# Tarjeta.net
KiCad netlist of a schematic drawn in EAGLE
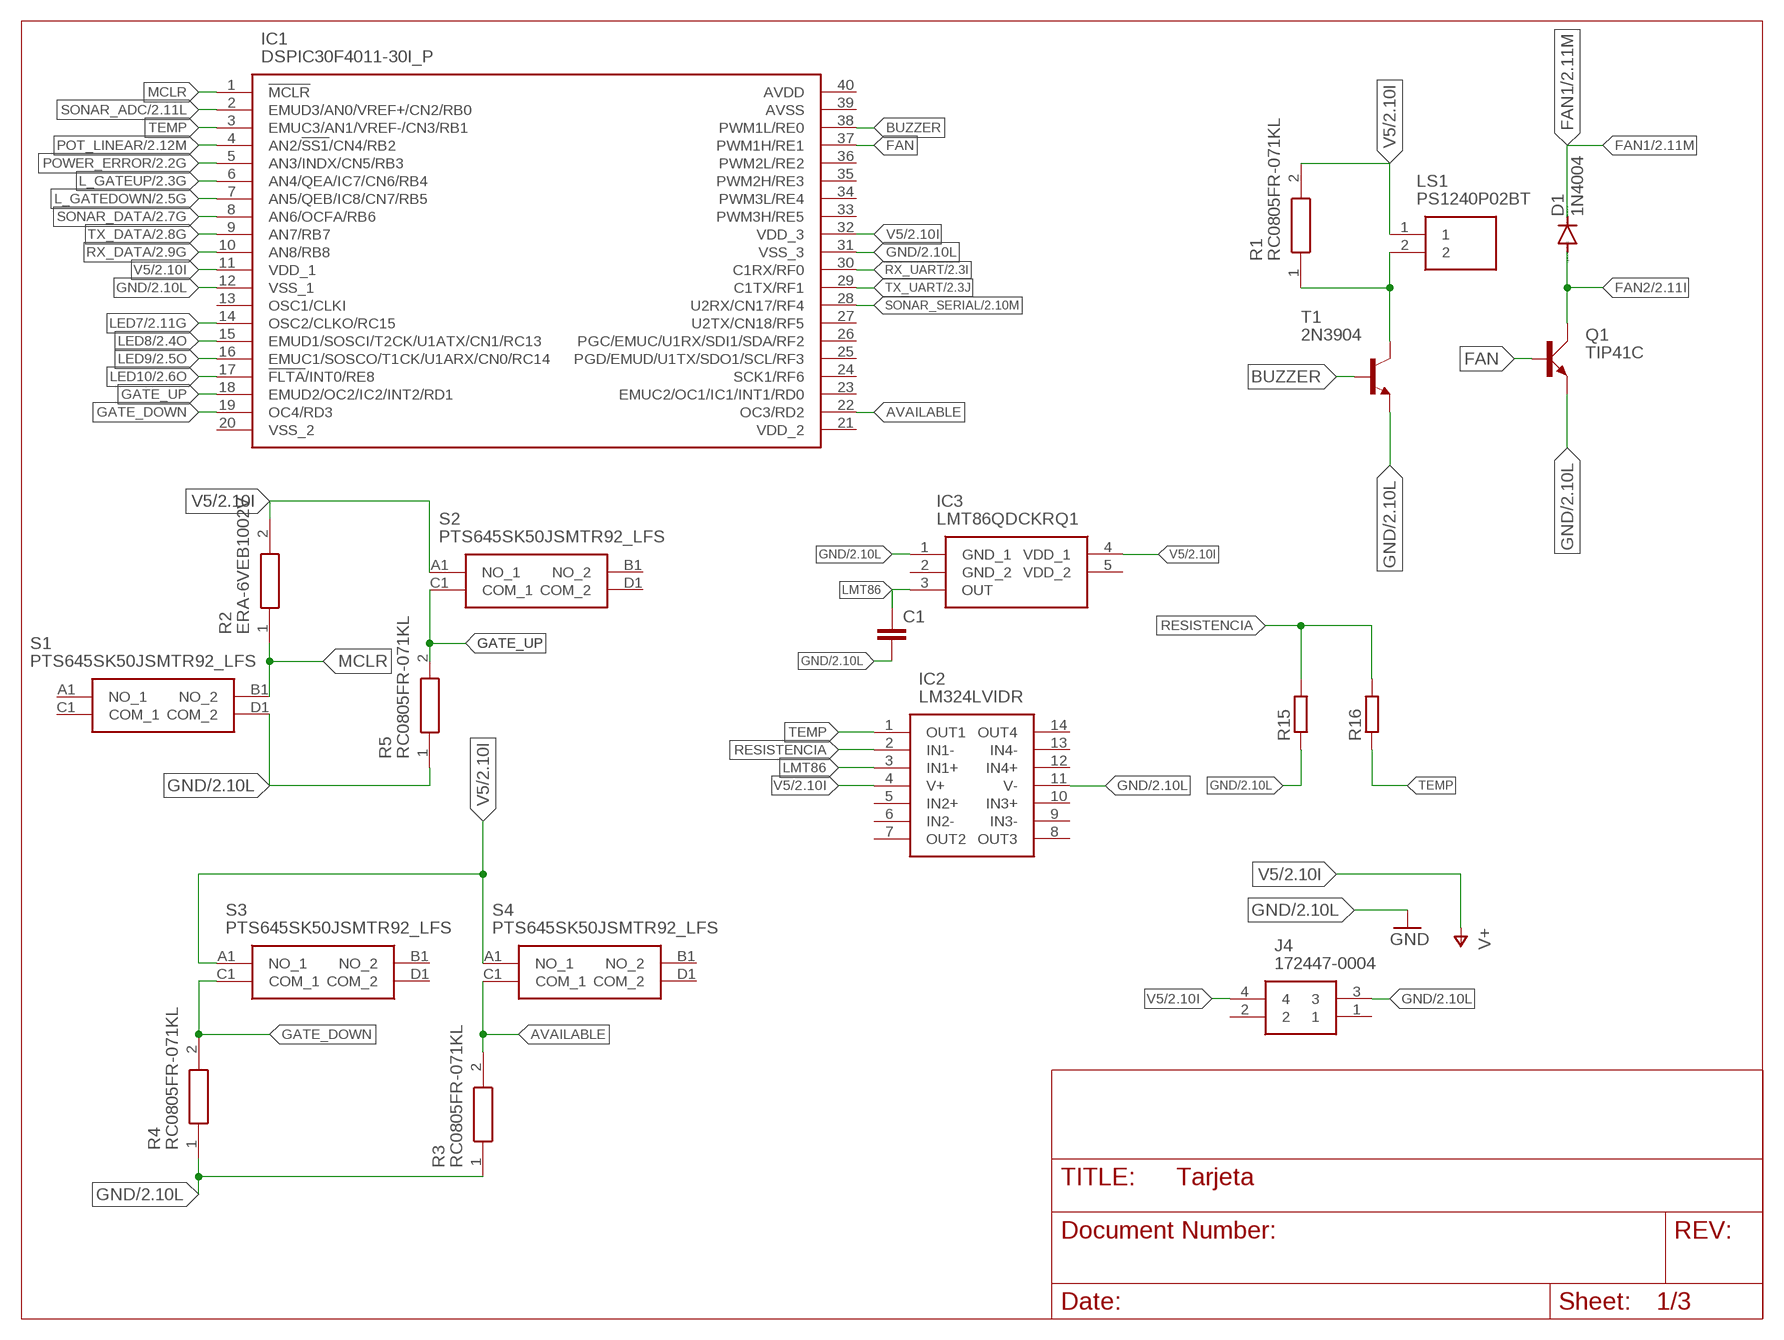
[diagram p0: schematic, sheet 1]
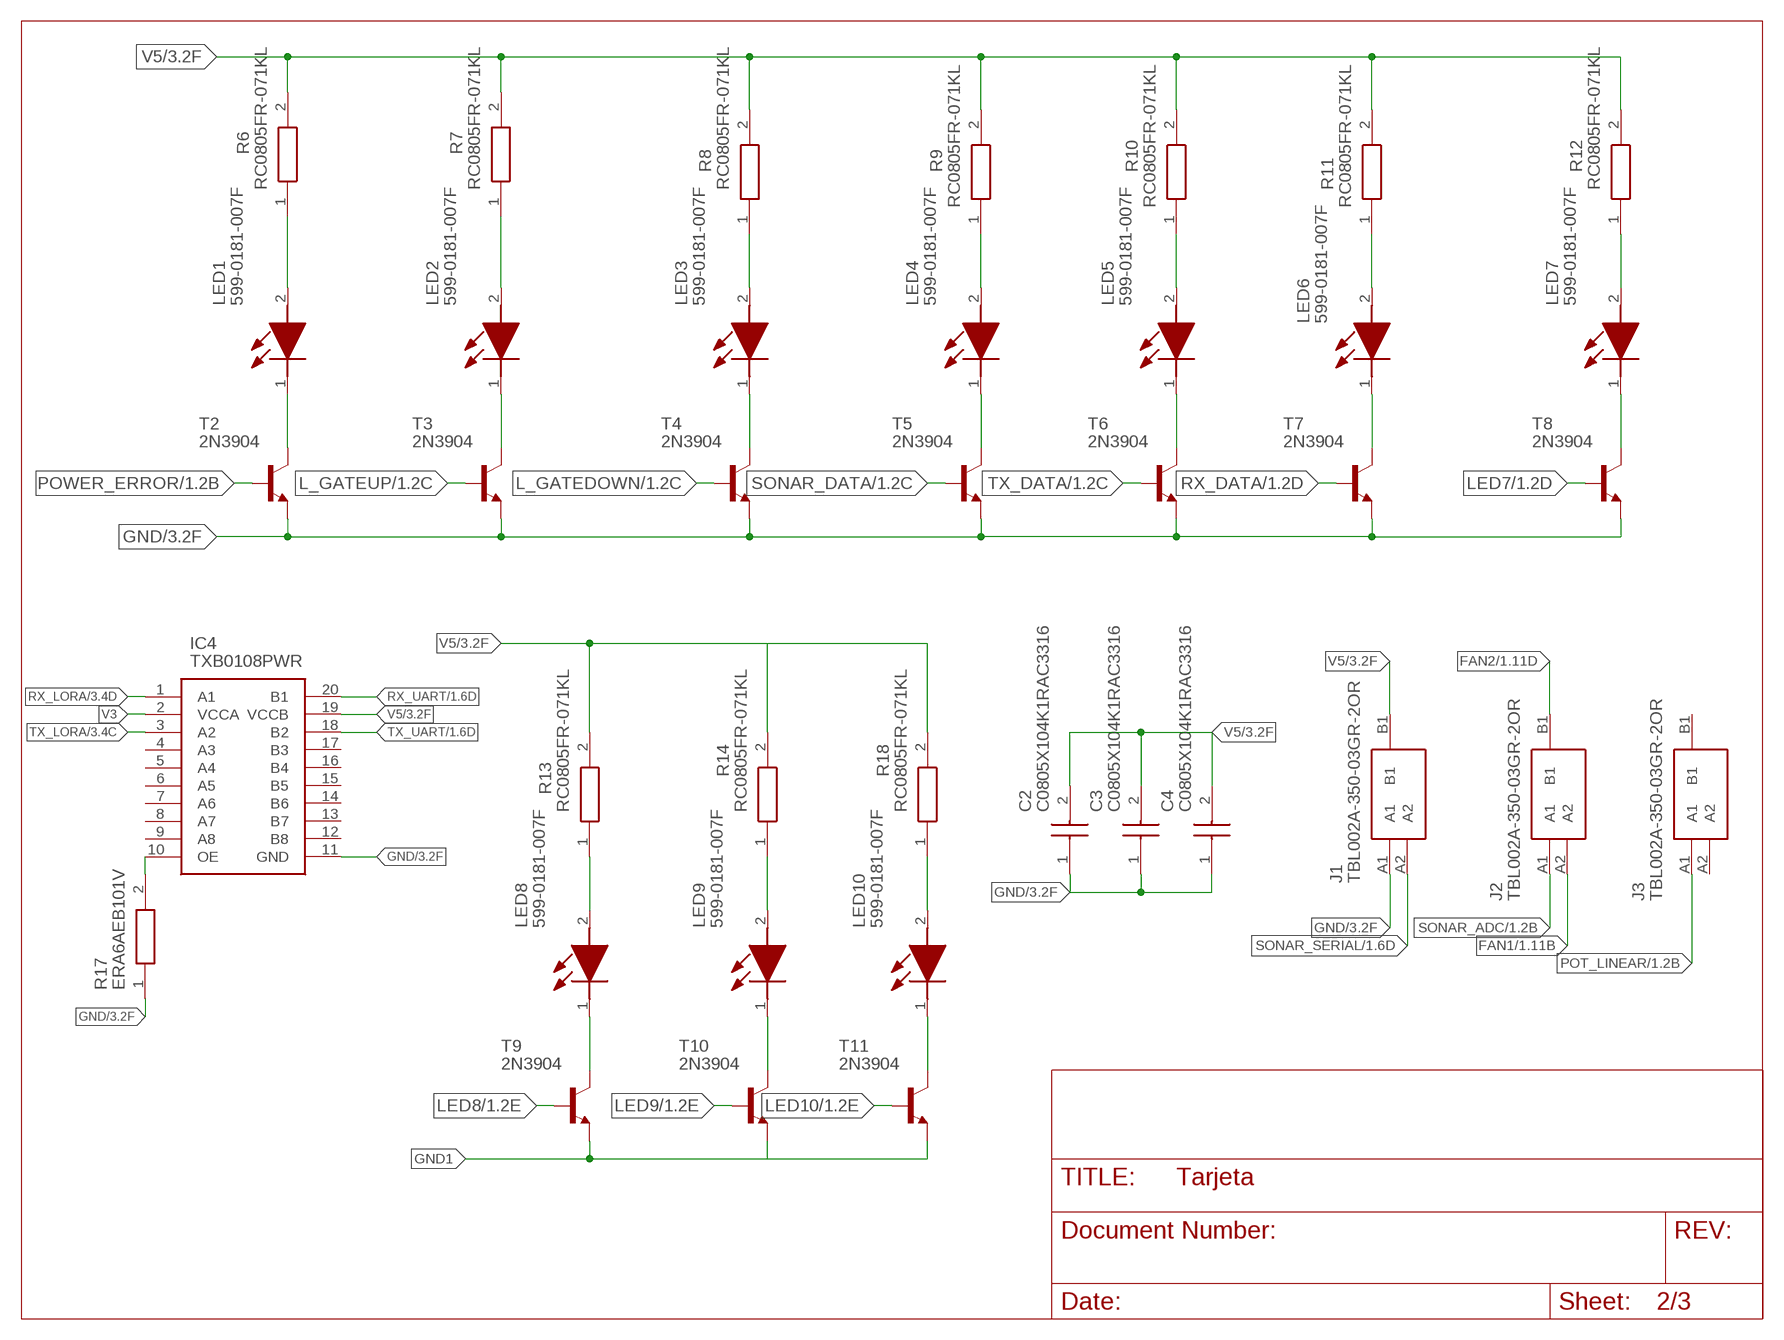
[diagram p1: schematic, sheet 2]
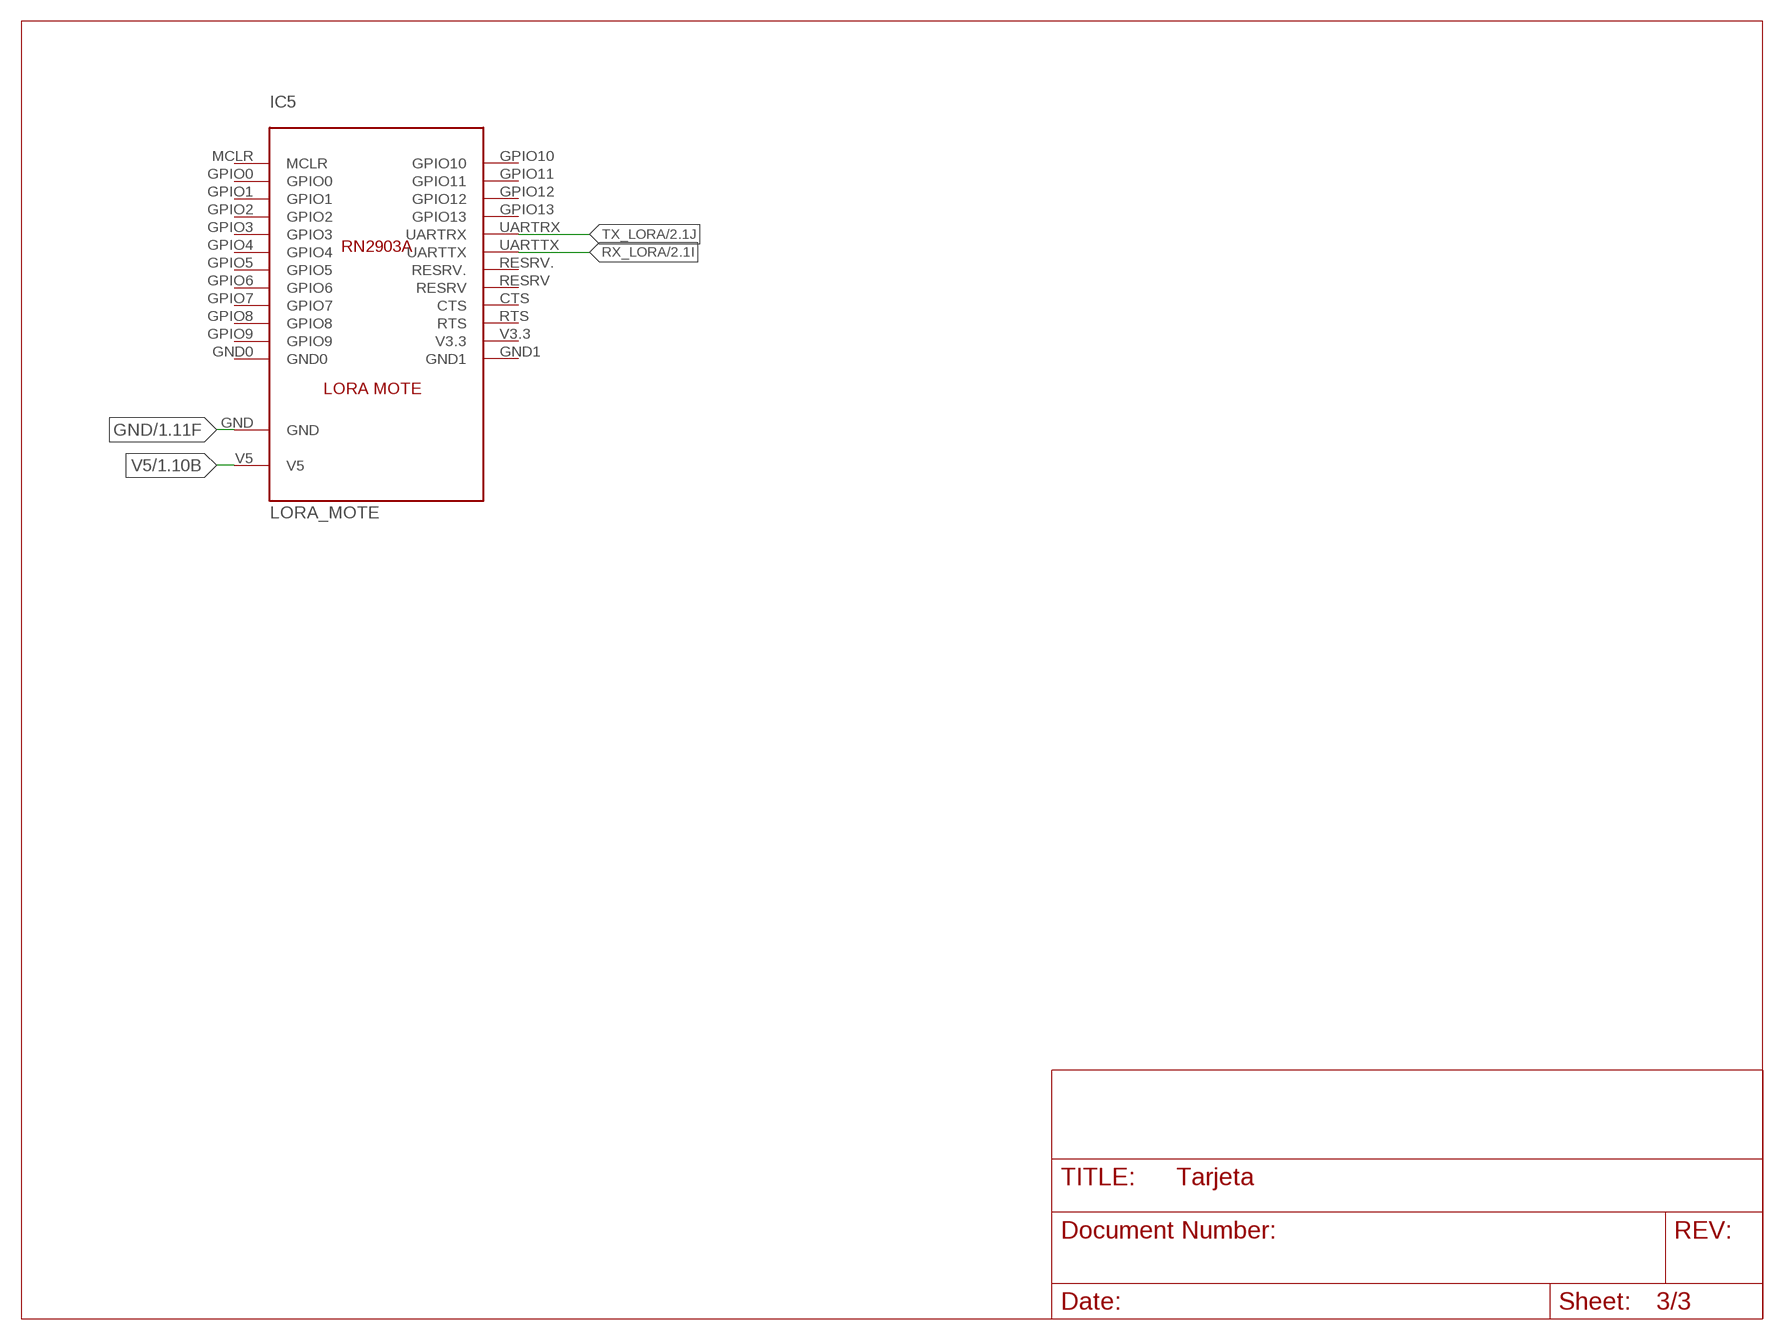
[diagram p2: schematic, sheet 3]

(export (version "E")
  (design (tool "Eeschema 10.0.6"))
  (components
    (comp (ref "C2")
      (value "C0805X104K1RAC3316")
      (footprint "eagle-import:CAPC2012X100N")
      (fields (field (name "MOUSER_PART_NUMBER") "80-C0805X104K1R3316"))
      (libsource (lib "eagle-import") (part "C0805X104K1RAC3316"))
    )
    (comp (ref "C3")
      (value "C0805X104K1RAC3316")
      (footprint "eagle-import:CAPC2012X100N")
      (fields (field (name "MOUSER_PART_NUMBER") "80-C0805X104K1R3316"))
      (libsource (lib "eagle-import") (part "C0805X104K1RAC3316"))
    )
    (comp (ref "C4")
      (value "C0805X104K1RAC3316")
      (footprint "eagle-import:CAPC2012X100N")
      (fields (field (name "MOUSER_PART_NUMBER") "80-C0805X104K1R3316"))
      (libsource (lib "eagle-import") (part "C0805X104K1RAC3316"))
    )
    (comp (ref "IC4")
      (value "TXB0108PWR")
      (footprint "eagle-import:SOP65P640X120-20N")
      (fields (field (name "MOUSER_PART_NUMBER") "595-TXB0108PWR"))
      (libsource (lib "eagle-import") (part "TXB0108PWR"))
    )
    (comp (ref "J1")
      (value "TBL002A-350-03GR-2OR")
      (footprint "eagle-import:TBL002A35003GR2OR")
      (fields (field (name "MOUSER_PART_NUMBER") "490-TBL002A3503GR2OR"))
      (libsource (lib "eagle-import") (part "TBL002A-350-03GR-2OR"))
    )
    (comp (ref "J2")
      (value "TBL002A-350-03GR-2OR")
      (footprint "eagle-import:TBL002A35003GR2OR")
      (fields (field (name "MOUSER_PART_NUMBER") "490-TBL002A3503GR2OR"))
      (libsource (lib "eagle-import") (part "TBL002A-350-03GR-2OR"))
    )
    (comp (ref "J3")
      (value "TBL002A-350-03GR-2OR")
      (footprint "eagle-import:TBL002A35003GR2OR")
      (fields (field (name "MOUSER_PART_NUMBER") "490-TBL002A3503GR2OR"))
      (libsource (lib "eagle-import") (part "TBL002A-350-03GR-2OR"))
    )
    (comp (ref "LED1")
      (value "599-0181-007F")
      (footprint "eagle-import:LEDC2012X70N")
      (fields (field (name "MOUSER_PART_NUMBER") "645-599-0181-007F"))
      (libsource (lib "eagle-import") (part "599-0181-007F"))
    )
    (comp (ref "LED2")
      (value "599-0181-007F")
      (footprint "eagle-import:LEDC2012X70N")
      (fields (field (name "MOUSER_PART_NUMBER") "645-599-0181-007F"))
      (libsource (lib "eagle-import") (part "599-0181-007F"))
    )
    (comp (ref "LED3")
      (value "599-0181-007F")
      (footprint "eagle-import:LEDC2012X70N")
      (fields (field (name "MOUSER_PART_NUMBER") "645-599-0181-007F"))
      (libsource (lib "eagle-import") (part "599-0181-007F"))
    )
    (comp (ref "LED4")
      (value "599-0181-007F")
      (footprint "eagle-import:LEDC2012X70N")
      (fields (field (name "MOUSER_PART_NUMBER") "645-599-0181-007F"))
      (libsource (lib "eagle-import") (part "599-0181-007F"))
    )
    (comp (ref "LED5")
      (value "599-0181-007F")
      (footprint "eagle-import:LEDC2012X70N")
      (fields (field (name "MOUSER_PART_NUMBER") "645-599-0181-007F"))
      (libsource (lib "eagle-import") (part "599-0181-007F"))
    )
    (comp (ref "LED6")
      (value "599-0181-007F")
      (footprint "eagle-import:LEDC2012X70N")
      (fields (field (name "MOUSER_PART_NUMBER") "645-599-0181-007F"))
      (libsource (lib "eagle-import") (part "599-0181-007F"))
    )
    (comp (ref "LED7")
      (value "599-0181-007F")
      (footprint "eagle-import:LEDC2012X70N")
      (fields (field (name "MOUSER_PART_NUMBER") "645-599-0181-007F"))
      (libsource (lib "eagle-import") (part "599-0181-007F"))
    )
    (comp (ref "LED8")
      (value "599-0181-007F")
      (footprint "eagle-import:LEDC2012X70N")
      (fields (field (name "MOUSER_PART_NUMBER") "645-599-0181-007F"))
      (libsource (lib "eagle-import") (part "599-0181-007F"))
    )
    (comp (ref "LED9")
      (value "599-0181-007F")
      (footprint "eagle-import:LEDC2012X70N")
      (fields (field (name "MOUSER_PART_NUMBER") "645-599-0181-007F"))
      (libsource (lib "eagle-import") (part "599-0181-007F"))
    )
    (comp (ref "LED10")
      (value "599-0181-007F")
      (footprint "eagle-import:LEDC2012X70N")
      (fields (field (name "MOUSER_PART_NUMBER") "645-599-0181-007F"))
      (libsource (lib "eagle-import") (part "599-0181-007F"))
    )
    (comp (ref "R6")
      (value "RC0805FR-071KL")
      (footprint "eagle-import:RESC2012X60N")
      (fields (field (name "MOUSER_PART_NUMBER") "603-RC0805FR-071KL"))
      (libsource (lib "eagle-import") (part "RC0805FR-071KL"))
    )
    (comp (ref "R7")
      (value "RC0805FR-071KL")
      (footprint "eagle-import:RESC2012X60N")
      (fields (field (name "MOUSER_PART_NUMBER") "603-RC0805FR-071KL"))
      (libsource (lib "eagle-import") (part "RC0805FR-071KL"))
    )
    (comp (ref "R8")
      (value "RC0805FR-071KL")
      (footprint "eagle-import:RESC2012X60N")
      (fields (field (name "MOUSER_PART_NUMBER") "603-RC0805FR-071KL"))
      (libsource (lib "eagle-import") (part "RC0805FR-071KL"))
    )
    (comp (ref "R9")
      (value "RC0805FR-071KL")
      (footprint "eagle-import:RESC2012X60N")
      (fields (field (name "MOUSER_PART_NUMBER") "603-RC0805FR-071KL"))
      (libsource (lib "eagle-import") (part "RC0805FR-071KL"))
    )
    (comp (ref "R10")
      (value "RC0805FR-071KL")
      (footprint "eagle-import:RESC2012X60N")
      (fields (field (name "MOUSER_PART_NUMBER") "603-RC0805FR-071KL"))
      (libsource (lib "eagle-import") (part "RC0805FR-071KL"))
    )
    (comp (ref "R11")
      (value "RC0805FR-071KL")
      (footprint "eagle-import:RESC2012X60N")
      (fields (field (name "MOUSER_PART_NUMBER") "603-RC0805FR-071KL"))
      (libsource (lib "eagle-import") (part "RC0805FR-071KL"))
    )
    (comp (ref "R12")
      (value "RC0805FR-071KL")
      (footprint "eagle-import:RESC2012X60N")
      (fields (field (name "MOUSER_PART_NUMBER") "603-RC0805FR-071KL"))
      (libsource (lib "eagle-import") (part "RC0805FR-071KL"))
    )
    (comp (ref "R13")
      (value "RC0805FR-071KL")
      (footprint "eagle-import:RESC2012X60N")
      (fields (field (name "MOUSER_PART_NUMBER") "603-RC0805FR-071KL"))
      (libsource (lib "eagle-import") (part "RC0805FR-071KL"))
    )
    (comp (ref "R14")
      (value "RC0805FR-071KL")
      (footprint "eagle-import:RESC2012X60N")
      (fields (field (name "MOUSER_PART_NUMBER") "603-RC0805FR-071KL"))
      (libsource (lib "eagle-import") (part "RC0805FR-071KL"))
    )
    (comp (ref "R17")
      (value "ERA6AEB101V")
      (footprint "eagle-import:RESC2012X60N")
      (libsource (lib "eagle-import") (part "ERA6AEB101V"))
    )
    (comp (ref "R18")
      (value "RC0805FR-071KL")
      (footprint "eagle-import:RESC2012X60N")
      (fields (field (name "MOUSER_PART_NUMBER") "603-RC0805FR-071KL"))
      (libsource (lib "eagle-import") (part "RC0805FR-071KL"))
    )
    (comp (ref "T2")
      (value "2N3904")
      (footprint "eagle-import:TO92")
      (libsource (lib "eagle-import") (part "2N3904"))
    )
    (comp (ref "T3")
      (value "2N3904")
      (footprint "eagle-import:TO92")
      (libsource (lib "eagle-import") (part "2N3904"))
    )
    (comp (ref "T4")
      (value "2N3904")
      (footprint "eagle-import:TO92")
      (libsource (lib "eagle-import") (part "2N3904"))
    )
    (comp (ref "T5")
      (value "2N3904")
      (footprint "eagle-import:TO92")
      (libsource (lib "eagle-import") (part "2N3904"))
    )
    (comp (ref "T6")
      (value "2N3904")
      (footprint "eagle-import:TO92")
      (libsource (lib "eagle-import") (part "2N3904"))
    )
    (comp (ref "T7")
      (value "2N3904")
      (footprint "eagle-import:TO92")
      (libsource (lib "eagle-import") (part "2N3904"))
    )
    (comp (ref "T8")
      (value "2N3904")
      (footprint "eagle-import:TO92")
      (libsource (lib "eagle-import") (part "2N3904"))
    )
    (comp (ref "T9")
      (value "2N3904")
      (footprint "eagle-import:TO92")
      (libsource (lib "eagle-import") (part "2N3904"))
    )
    (comp (ref "T10")
      (value "2N3904")
      (footprint "eagle-import:TO92")
      (libsource (lib "eagle-import") (part "2N3904"))
    )
    (comp (ref "T11")
      (value "2N3904")
      (footprint "eagle-import:TO92")
      (libsource (lib "eagle-import") (part "2N3904"))
    )
    (comp (ref "C1")
      (value "C-EUC0805")
      (footprint "eagle-import:C0805")
      (libsource (lib "eagle-import") (part "C-EUC0805"))
    )
    (comp (ref "D1")
      (value "1N4004")
      (footprint "eagle-import:DO41-10")
      (libsource (lib "eagle-import") (part "1N4004"))
    )
    (comp (ref "IC1")
      (value "DSPIC30F4011-30I_P")
      (footprint "eagle-import:DIP1543W58P254L5175H635Q40N")
      (fields
        (field (name "ARROW_PART_NUMBER") "dsPIC30F4011-30I/P")
        (field (name "MANUFACTURER_PART_NUMBER") "DSPIC30F4011-30I/P")
        (field (name "MOUSER_PART_NUMBER") "579-30F4011-30I/P")
      )
      (libsource (lib "eagle-import") (part "DSPIC30F4011-30I_P"))
    )
    (comp (ref "IC2")
      (value "LM324LVIDR")
      (footprint "eagle-import:SOIC127P600X175-14N")
      (fields (field (name "MOUSER_PART_NUMBER") "595-LM324LVIDR"))
      (libsource (lib "eagle-import") (part "LM324LVIDR"))
    )
    (comp (ref "IC3")
      (value "LMT86QDCKRQ1")
      (footprint "eagle-import:SOT65P210X110-5N")
      (fields (field (name "MOUSER_PART_NUMBER") "595-LMT86QDCKRQ1"))
      (libsource (lib "eagle-import") (part "LMT86QDCKRQ1"))
    )
    (comp (ref "J4")
      (value "172447-0004")
      (footprint "eagle-import:1724470004")
      (fields (field (name "MOUSER_PART_NUMBER") "538-172447-0004"))
      (libsource (lib "eagle-import") (part "172447-0004"))
    )
    (comp (ref "LS1")
      (value "PS1240P02BT")
      (footprint "eagle-import:PS1240P02BT")
      (fields (field (name "MOUSER_PART_NUMBER") "810-PS1240P02BT"))
      (libsource (lib "eagle-import") (part "PS1240P02BT"))
    )
    (comp (ref "Q1")
      (value "TIP41C")
      (footprint "eagle-import:TO220AV")
      (libsource (lib "eagle-import") (part "TIP41C"))
    )
    (comp (ref "R1")
      (value "RC0805FR-071KL")
      (footprint "eagle-import:RESC2012X60N")
      (fields (field (name "MOUSER_PART_NUMBER") "603-RC0805FR-071KL"))
      (libsource (lib "eagle-import") (part "RC0805FR-071KL"))
    )
    (comp (ref "R2")
      (value "ERA-6VEB1002V")
      (footprint "eagle-import:RESC2012X65N")
      (fields (field (name "MOUSER_PART_NUMBER") "667-ERA-6VEB1002V"))
      (libsource (lib "eagle-import") (part "ERA-6VEB1002V"))
    )
    (comp (ref "R3")
      (value "RC0805FR-071KL")
      (footprint "eagle-import:RESC2012X60N")
      (fields (field (name "MOUSER_PART_NUMBER") "603-RC0805FR-071KL"))
      (libsource (lib "eagle-import") (part "RC0805FR-071KL"))
    )
    (comp (ref "R4")
      (value "RC0805FR-071KL")
      (footprint "eagle-import:RESC2012X60N")
      (fields (field (name "MOUSER_PART_NUMBER") "603-RC0805FR-071KL"))
      (libsource (lib "eagle-import") (part "RC0805FR-071KL"))
    )
    (comp (ref "R5")
      (value "RC0805FR-071KL")
      (footprint "eagle-import:RESC2012X60N")
      (fields (field (name "MOUSER_PART_NUMBER") "603-RC0805FR-071KL"))
      (libsource (lib "eagle-import") (part "RC0805FR-071KL"))
    )
    (comp (ref "R15")
      (value "R-EU_0204/7")
      (footprint "eagle-import:0204_7")
      (libsource (lib "eagle-import") (part "R-EU_0204/7"))
    )
    (comp (ref "R16")
      (value "R-EU_0204/7")
      (footprint "eagle-import:0204_7")
      (libsource (lib "eagle-import") (part "R-EU_0204/7"))
    )
    (comp (ref "S1")
      (value "PTS645SK50JSMTR92_LFS")
      (footprint "eagle-import:PTS645SK50JSMTR92LFS")
      (fields
        (field (name "MANUFACTURER_PART_NUMBER") "PTS645SK50JSMTR92 LFS")
        (field (name "MOUSER_PART_NUMBER") "611-SK50JSMTR92LFS")
      )
      (libsource (lib "eagle-import") (part "PTS645SK50JSMTR92_LFS"))
    )
    (comp (ref "S2")
      (value "PTS645SK50JSMTR92_LFS")
      (footprint "eagle-import:PTS645SK50JSMTR92LFS")
      (fields
        (field (name "MANUFACTURER_PART_NUMBER") "PTS645SK50JSMTR92 LFS")
        (field (name "MOUSER_PART_NUMBER") "611-SK50JSMTR92LFS")
      )
      (libsource (lib "eagle-import") (part "PTS645SK50JSMTR92_LFS"))
    )
    (comp (ref "S3")
      (value "PTS645SK50JSMTR92_LFS")
      (footprint "eagle-import:PTS645SK50JSMTR92LFS")
      (fields
        (field (name "MANUFACTURER_PART_NUMBER") "PTS645SK50JSMTR92 LFS")
        (field (name "MOUSER_PART_NUMBER") "611-SK50JSMTR92LFS")
      )
      (libsource (lib "eagle-import") (part "PTS645SK50JSMTR92_LFS"))
    )
    (comp (ref "S4")
      (value "PTS645SK50JSMTR92_LFS")
      (footprint "eagle-import:PTS645SK50JSMTR92LFS")
      (fields
        (field (name "MANUFACTURER_PART_NUMBER") "PTS645SK50JSMTR92 LFS")
        (field (name "MOUSER_PART_NUMBER") "611-SK50JSMTR92LFS")
      )
      (libsource (lib "eagle-import") (part "PTS645SK50JSMTR92_LFS"))
    )
    (comp (ref "T1")
      (value "2N3904")
      (footprint "eagle-import:TO92")
      (libsource (lib "eagle-import") (part "2N3904"))
    )
    (comp (ref "IC5")
      (value "LORA_MOTE")
      (footprint "eagle-import:LORA_MOTE_RN2903")
      (libsource (lib "eagle-import") (part "LORA_MOTE"))
    )
  )
  (nets
    (net (code "1") (name "AVAILABLE") (class "Default")
      (node (ref "IC1") (pin "22") (pinfunction "OC3/RD2_22") (pintype "bidirectional"))
      (node (ref "R3") (pin "2") (pinfunction "2_2") (pintype "bidirectional"))
      (node (ref "S4") (pin "C1") (pinfunction "COM_1_C1") (pintype "bidirectional"))
    )
    (net (code "2") (name "BUZZER") (class "Default")
      (node (ref "IC1") (pin "38") (pinfunction "PWM1L/RE0_38") (pintype "bidirectional"))
      (node (ref "T1") (pin "2") (pinfunction "B_2") (pintype "passive"))
    )
    (net (code "3") (name "FAN") (class "Default")
      (node (ref "IC1") (pin "37") (pinfunction "PWM1H/RE1_37") (pintype "bidirectional"))
      (node (ref "Q1") (pin "B") (pinfunction "B_B") (pintype "passive"))
    )
    (net (code "4") (name "FAN1") (class "Default")
      (node (ref "D1") (pin "C") (pinfunction "C_C") (pintype "passive"))
      (node (ref "J2") (pin "A2") (pinfunction "A2_A2") (pintype "bidirectional"))
    )
    (net (code "5") (name "FAN2") (class "Default")
      (node (ref "D1") (pin "A") (pinfunction "A_A") (pintype "passive"))
      (node (ref "J2") (pin "B1") (pinfunction "B1_B1") (pintype "bidirectional"))
      (node (ref "Q1") (pin "C") (pinfunction "C_C") (pintype "passive"))
    )
    (net (code "6") (name "GATE_DOWN") (class "Default")
      (node (ref "IC1") (pin "19") (pinfunction "OC4/RD3_19") (pintype "bidirectional"))
      (node (ref "R4") (pin "2") (pinfunction "2_2") (pintype "bidirectional"))
      (node (ref "S3") (pin "C1") (pinfunction "COM_1_C1") (pintype "bidirectional"))
    )
    (net (code "7") (name "GATE_UP") (class "Default")
      (node (ref "IC1") (pin "18") (pinfunction "EMUD2/OC2/IC2/INT2/RD1_18") (pintype "bidirectional"))
      (node (ref "R5") (pin "2") (pinfunction "2_2") (pintype "bidirectional"))
      (node (ref "S2") (pin "C1") (pinfunction "COM_1_C1") (pintype "bidirectional"))
    )
    (net (code "8") (name "GND") (class "Default")
      (node (ref "C1") (pin "2") (pinfunction "2_2") (pintype "passive"))
      (node (ref "C2") (pin "1") (pinfunction "1_1") (pintype "bidirectional"))
      (node (ref "C3") (pin "1") (pinfunction "1_1") (pintype "bidirectional"))
      (node (ref "C4") (pin "1") (pinfunction "1_1") (pintype "bidirectional"))
      (node (ref "IC1") (pin "12") (pinfunction "VSS_1_12") (pintype "bidirectional"))
      (node (ref "IC1") (pin "31") (pinfunction "VSS_3_31") (pintype "bidirectional"))
      (node (ref "IC2") (pin "11") (pinfunction "V-_11") (pintype "bidirectional"))
      (node (ref "IC3") (pin "1") (pinfunction "GND_1_1") (pintype "bidirectional"))
      (node (ref "IC4") (pin "11") (pinfunction "GND_11") (pintype "bidirectional"))
      (node (ref "IC5") (pin "GND") (pinfunction "GND_GND") (pintype "bidirectional"))
      (node (ref "J1") (pin "A1") (pinfunction "A1_A1") (pintype "bidirectional"))
      (node (ref "J4") (pin "3") (pinfunction "3_3") (pintype "bidirectional"))
      (node (ref "Q1") (pin "E") (pinfunction "E_E") (pintype "passive"))
      (node (ref "R15") (pin "1") (pinfunction "1_1") (pintype "passive"))
      (node (ref "R17") (pin "1") (pinfunction "1_1") (pintype "bidirectional"))
      (node (ref "R3") (pin "1") (pinfunction "1_1") (pintype "bidirectional"))
      (node (ref "R4") (pin "1") (pinfunction "1_1") (pintype "bidirectional"))
      (node (ref "R5") (pin "1") (pinfunction "1_1") (pintype "bidirectional"))
      (node (ref "S1") (pin "D1") (pinfunction "COM_2_D1") (pintype "bidirectional"))
      (node (ref "T1") (pin "3") (pinfunction "E_3") (pintype "passive"))
      (node (ref "T2") (pin "3") (pinfunction "E_3") (pintype "passive"))
      (node (ref "T3") (pin "3") (pinfunction "E_3") (pintype "passive"))
      (node (ref "T4") (pin "3") (pinfunction "E_3") (pintype "passive"))
      (node (ref "T5") (pin "3") (pinfunction "E_3") (pintype "passive"))
      (node (ref "T6") (pin "3") (pinfunction "E_3") (pintype "passive"))
      (node (ref "T7") (pin "3") (pinfunction "E_3") (pintype "passive"))
      (node (ref "T8") (pin "3") (pinfunction "E_3") (pintype "passive"))
    )
    (net (code "9") (name "GND1") (class "Default")
      (node (ref "T10") (pin "3") (pinfunction "E_3") (pintype "passive"))
      (node (ref "T9") (pin "3") (pinfunction "E_3") (pintype "passive"))
    )
    (net (code "10") (name "LED7") (class "Default")
      (node (ref "IC1") (pin "14") (pinfunction "OSC2/CLKO/RC15_14") (pintype "bidirectional"))
      (node (ref "T8") (pin "2") (pinfunction "B_2") (pintype "passive"))
    )
    (net (code "11") (name "LED8") (class "Default")
      (node (ref "IC1") (pin "15") (pinfunction "EMUD1/SOSCI/T2CK/U1ATX/CN1/RC13_15") (pintype "bidirectional"))
      (node (ref "T9") (pin "2") (pinfunction "B_2") (pintype "passive"))
    )
    (net (code "12") (name "LED9") (class "Default")
      (node (ref "IC1") (pin "16") (pinfunction "EMUC1/SOSCO/T1CK/U1ARX/CN0/RC14_16") (pintype "bidirectional"))
      (node (ref "T10") (pin "2") (pinfunction "B_2") (pintype "passive"))
    )
    (net (code "13") (name "LED10") (class "Default")
      (node (ref "IC1") (pin "17") (pinfunction "~{FLTA}/INT0/RE8_17") (pintype "bidirectional"))
      (node (ref "T11") (pin "2") (pinfunction "B_2") (pintype "passive"))
    )
    (net (code "14") (name "LMT86") (class "Default")
      (node (ref "C1") (pin "1") (pinfunction "1_1") (pintype "passive"))
      (node (ref "IC2") (pin "3") (pinfunction "IN1+_3") (pintype "bidirectional"))
      (node (ref "IC3") (pin "3") (pinfunction "OUT_3") (pintype "bidirectional"))
    )
    (net (code "15") (name "L_GATEDOWN") (class "Default")
      (node (ref "IC1") (pin "7") (pinfunction "AN5/QEB/IC8/CN7/RB5_7") (pintype "bidirectional"))
      (node (ref "T4") (pin "2") (pinfunction "B_2") (pintype "passive"))
    )
    (net (code "16") (name "L_GATEUP") (class "Default")
      (node (ref "IC1") (pin "6") (pinfunction "AN4/QEA/IC7/CN6/RB4_6") (pintype "bidirectional"))
      (node (ref "T3") (pin "2") (pinfunction "B_2") (pintype "passive"))
    )
    (net (code "17") (name "MCLR") (class "Default")
      (node (ref "IC1") (pin "1") (pinfunction "~{MCLR}_1") (pintype "bidirectional"))
      (node (ref "R2") (pin "1") (pinfunction "1_1") (pintype "bidirectional"))
      (node (ref "S1") (pin "B1") (pinfunction "NO_2_B1") (pintype "bidirectional"))
    )
    (net (code "18") (name "Net-(IC4-OE)") (class "Default")
      (node (ref "IC4") (pin "10") (pinfunction "OE_10") (pintype "bidirectional"))
      (node (ref "R17") (pin "2") (pinfunction "2_2") (pintype "bidirectional"))
    )
    (net (code "19") (name "Net-(LED1-A)") (class "Default")
      (node (ref "LED1") (pin "2") (pinfunction "A_2") (pintype "bidirectional"))
      (node (ref "R6") (pin "1") (pinfunction "1_1") (pintype "bidirectional"))
    )
    (net (code "20") (name "Net-(LED1-K)") (class "Default")
      (node (ref "LED1") (pin "1") (pinfunction "K_1") (pintype "bidirectional"))
      (node (ref "T2") (pin "1") (pinfunction "C_1") (pintype "passive"))
    )
    (net (code "21") (name "Net-(LED2-A)") (class "Default")
      (node (ref "LED2") (pin "2") (pinfunction "A_2") (pintype "bidirectional"))
      (node (ref "R7") (pin "1") (pinfunction "1_1") (pintype "bidirectional"))
    )
    (net (code "22") (name "Net-(LED2-K)") (class "Default")
      (node (ref "LED2") (pin "1") (pinfunction "K_1") (pintype "bidirectional"))
      (node (ref "T3") (pin "1") (pinfunction "C_1") (pintype "passive"))
    )
    (net (code "23") (name "Net-(LED3-A)") (class "Default")
      (node (ref "LED3") (pin "2") (pinfunction "A_2") (pintype "bidirectional"))
      (node (ref "R8") (pin "1") (pinfunction "1_1") (pintype "bidirectional"))
    )
    (net (code "24") (name "Net-(LED3-K)") (class "Default")
      (node (ref "LED3") (pin "1") (pinfunction "K_1") (pintype "bidirectional"))
      (node (ref "T4") (pin "1") (pinfunction "C_1") (pintype "passive"))
    )
    (net (code "25") (name "Net-(LED4-A)") (class "Default")
      (node (ref "LED4") (pin "2") (pinfunction "A_2") (pintype "bidirectional"))
      (node (ref "R9") (pin "1") (pinfunction "1_1") (pintype "bidirectional"))
    )
    (net (code "26") (name "Net-(LED4-K)") (class "Default")
      (node (ref "LED4") (pin "1") (pinfunction "K_1") (pintype "bidirectional"))
      (node (ref "T5") (pin "1") (pinfunction "C_1") (pintype "passive"))
    )
    (net (code "27") (name "Net-(LED5-A)") (class "Default")
      (node (ref "LED5") (pin "2") (pinfunction "A_2") (pintype "bidirectional"))
      (node (ref "R10") (pin "1") (pinfunction "1_1") (pintype "bidirectional"))
    )
    (net (code "28") (name "Net-(LED5-K)") (class "Default")
      (node (ref "LED5") (pin "1") (pinfunction "K_1") (pintype "bidirectional"))
      (node (ref "T6") (pin "1") (pinfunction "C_1") (pintype "passive"))
    )
    (net (code "29") (name "Net-(LED6-A)") (class "Default")
      (node (ref "LED6") (pin "2") (pinfunction "A_2") (pintype "bidirectional"))
      (node (ref "R11") (pin "1") (pinfunction "1_1") (pintype "bidirectional"))
    )
    (net (code "30") (name "Net-(LED6-K)") (class "Default")
      (node (ref "LED6") (pin "1") (pinfunction "K_1") (pintype "bidirectional"))
      (node (ref "T7") (pin "1") (pinfunction "C_1") (pintype "passive"))
    )
    (net (code "31") (name "Net-(LED7-A)") (class "Default")
      (node (ref "LED7") (pin "2") (pinfunction "A_2") (pintype "bidirectional"))
      (node (ref "R12") (pin "1") (pinfunction "1_1") (pintype "bidirectional"))
    )
    (net (code "32") (name "Net-(LED7-K)") (class "Default")
      (node (ref "LED7") (pin "1") (pinfunction "K_1") (pintype "bidirectional"))
      (node (ref "T8") (pin "1") (pinfunction "C_1") (pintype "passive"))
    )
    (net (code "33") (name "Net-(LED8-A)") (class "Default")
      (node (ref "LED8") (pin "2") (pinfunction "A_2") (pintype "bidirectional"))
      (node (ref "R13") (pin "1") (pinfunction "1_1") (pintype "bidirectional"))
    )
    (net (code "34") (name "Net-(LED8-K)") (class "Default")
      (node (ref "LED8") (pin "1") (pinfunction "K_1") (pintype "bidirectional"))
      (node (ref "T9") (pin "1") (pinfunction "C_1") (pintype "passive"))
    )
    (net (code "35") (name "Net-(LED9-A)") (class "Default")
      (node (ref "LED9") (pin "2") (pinfunction "A_2") (pintype "bidirectional"))
      (node (ref "R14") (pin "1") (pinfunction "1_1") (pintype "bidirectional"))
    )
    (net (code "36") (name "Net-(LED9-K)") (class "Default")
      (node (ref "LED9") (pin "1") (pinfunction "K_1") (pintype "bidirectional"))
      (node (ref "T10") (pin "1") (pinfunction "C_1") (pintype "passive"))
    )
    (net (code "37") (name "Net-(LED10-A)") (class "Default")
      (node (ref "LED10") (pin "2") (pinfunction "A_2") (pintype "bidirectional"))
      (node (ref "R18") (pin "1") (pinfunction "1_1") (pintype "bidirectional"))
    )
    (net (code "38") (name "Net-(LED10-K)") (class "Default")
      (node (ref "LED10") (pin "1") (pinfunction "K_1") (pintype "bidirectional"))
      (node (ref "T11") (pin "1") (pinfunction "C_1") (pintype "passive"))
    )
    (net (code "39") (name "Net-(T1-C)") (class "Default")
      (node (ref "LS1") (pin "2") (pinfunction "2_2") (pintype "bidirectional"))
      (node (ref "R1") (pin "1") (pinfunction "1_1") (pintype "bidirectional"))
      (node (ref "T1") (pin "1") (pinfunction "C_1") (pintype "passive"))
    )
    (net (code "40") (name "POT_LINEAR") (class "Default")
      (node (ref "IC1") (pin "4") (pinfunction "AN2/~{SS1}/CN4/RB2_4") (pintype "bidirectional"))
      (node (ref "J3") (pin "A1") (pinfunction "A1_A1") (pintype "bidirectional"))
    )
    (net (code "41") (name "POWER_ERROR") (class "Default")
      (node (ref "IC1") (pin "5") (pinfunction "AN3/INDX/CN5/RB3_5") (pintype "bidirectional"))
      (node (ref "T2") (pin "2") (pinfunction "B_2") (pintype "passive"))
    )
    (net (code "42") (name "RESISTENCIA") (class "Default")
      (node (ref "IC2") (pin "2") (pinfunction "IN1-_2") (pintype "bidirectional"))
      (node (ref "R15") (pin "2") (pinfunction "2_2") (pintype "passive"))
      (node (ref "R16") (pin "2") (pinfunction "2_2") (pintype "passive"))
    )
    (net (code "43") (name "RX_DATA") (class "Default")
      (node (ref "IC1") (pin "10") (pinfunction "AN8/RB8_10") (pintype "bidirectional"))
      (node (ref "T7") (pin "2") (pinfunction "B_2") (pintype "passive"))
    )
    (net (code "44") (name "RX_LORA") (class "Default")
      (node (ref "IC4") (pin "1") (pinfunction "A1_1") (pintype "bidirectional"))
      (node (ref "IC5") (pin "UARTTX") (pinfunction "UARTTX_UARTTX") (pintype "bidirectional"))
    )
    (net (code "45") (name "RX_UART") (class "Default")
      (node (ref "IC1") (pin "30") (pinfunction "C1RX/RF0_30") (pintype "bidirectional"))
      (node (ref "IC4") (pin "20") (pinfunction "B1_20") (pintype "bidirectional"))
    )
    (net (code "46") (name "SONAR_ADC") (class "Default")
      (node (ref "IC1") (pin "2") (pinfunction "EMUD3/AN0/VREF+/CN2/RB0_2") (pintype "bidirectional"))
      (node (ref "J2") (pin "A1") (pinfunction "A1_A1") (pintype "bidirectional"))
    )
    (net (code "47") (name "SONAR_DATA") (class "Default")
      (node (ref "IC1") (pin "8") (pinfunction "AN6/OCFA/RB6_8") (pintype "bidirectional"))
      (node (ref "T5") (pin "2") (pinfunction "B_2") (pintype "passive"))
    )
    (net (code "48") (name "SONAR_SERIAL") (class "Default")
      (node (ref "IC1") (pin "28") (pinfunction "U2RX/CN17/RF4_28") (pintype "bidirectional"))
      (node (ref "J1") (pin "A2") (pinfunction "A2_A2") (pintype "bidirectional"))
    )
    (net (code "49") (name "TEMP") (class "Default")
      (node (ref "IC1") (pin "3") (pinfunction "EMUC3/AN1/VREF-/CN3/RB1_3") (pintype "bidirectional"))
      (node (ref "IC2") (pin "1") (pinfunction "OUT1_1") (pintype "bidirectional"))
      (node (ref "R16") (pin "1") (pinfunction "1_1") (pintype "passive"))
    )
    (net (code "50") (name "TX_DATA") (class "Default")
      (node (ref "IC1") (pin "9") (pinfunction "AN7/RB7_9") (pintype "bidirectional"))
      (node (ref "T6") (pin "2") (pinfunction "B_2") (pintype "passive"))
    )
    (net (code "51") (name "TX_LORA") (class "Default")
      (node (ref "IC4") (pin "3") (pinfunction "A2_3") (pintype "bidirectional"))
      (node (ref "IC5") (pin "UARTRX") (pinfunction "UARTRX_UARTRX") (pintype "bidirectional"))
    )
    (net (code "52") (name "TX_UART") (class "Default")
      (node (ref "IC1") (pin "29") (pinfunction "C1TX/RF1_29") (pintype "bidirectional"))
      (node (ref "IC4") (pin "18") (pinfunction "B2_18") (pintype "bidirectional"))
    )
    (net (code "53") (name "V3") (class "Default")
      (node (ref "IC4") (pin "2") (pinfunction "VCCA_2") (pintype "bidirectional"))
    )
    (net (code "54") (name "V5") (class "Default")
      (node (ref "C2") (pin "2") (pinfunction "2_2") (pintype "bidirectional"))
      (node (ref "C3") (pin "2") (pinfunction "2_2") (pintype "bidirectional"))
      (node (ref "C4") (pin "2") (pinfunction "2_2") (pintype "bidirectional"))
      (node (ref "IC1") (pin "11") (pinfunction "VDD_1_11") (pintype "bidirectional"))
      (node (ref "IC1") (pin "32") (pinfunction "VDD_3_32") (pintype "bidirectional"))
      (node (ref "IC2") (pin "4") (pinfunction "V+_4") (pintype "bidirectional"))
      (node (ref "IC3") (pin "4") (pinfunction "VDD_1_4") (pintype "bidirectional"))
      (node (ref "IC4") (pin "19") (pinfunction "VCCB_19") (pintype "bidirectional"))
      (node (ref "IC5") (pin "V5") (pinfunction "V5_V5") (pintype "bidirectional"))
      (node (ref "J1") (pin "B1") (pinfunction "B1_B1") (pintype "bidirectional"))
      (node (ref "J4") (pin "4") (pinfunction "4_4") (pintype "bidirectional"))
      (node (ref "LS1") (pin "1") (pinfunction "1_1") (pintype "bidirectional"))
      (node (ref "R1") (pin "2") (pinfunction "2_2") (pintype "bidirectional"))
      (node (ref "R10") (pin "2") (pinfunction "2_2") (pintype "bidirectional"))
      (node (ref "R11") (pin "2") (pinfunction "2_2") (pintype "bidirectional"))
      (node (ref "R12") (pin "2") (pinfunction "2_2") (pintype "bidirectional"))
      (node (ref "R13") (pin "2") (pinfunction "2_2") (pintype "bidirectional"))
      (node (ref "R14") (pin "2") (pinfunction "2_2") (pintype "bidirectional"))
      (node (ref "R2") (pin "2") (pinfunction "2_2") (pintype "bidirectional"))
      (node (ref "R6") (pin "2") (pinfunction "2_2") (pintype "bidirectional"))
      (node (ref "R7") (pin "2") (pinfunction "2_2") (pintype "bidirectional"))
      (node (ref "R8") (pin "2") (pinfunction "2_2") (pintype "bidirectional"))
      (node (ref "R9") (pin "2") (pinfunction "2_2") (pintype "bidirectional"))
      (node (ref "S2") (pin "A1") (pinfunction "NO_1_A1") (pintype "bidirectional"))
      (node (ref "S3") (pin "A1") (pinfunction "NO_1_A1") (pintype "bidirectional"))
      (node (ref "S4") (pin "A1") (pinfunction "NO_1_A1") (pintype "bidirectional"))
    )
    (net (code "55") (name "unconnected-(IC1-AVDD-Pad40)") (class "Default")
      (node (ref "IC1") (pin "40") (pinfunction "AVDD_40") (pintype "bidirectional"))
    )
    (net (code "56") (name "unconnected-(IC1-AVSS-Pad39)") (class "Default")
      (node (ref "IC1") (pin "39") (pinfunction "AVSS_39") (pintype "bidirectional"))
    )
    (net (code "57") (name "unconnected-(IC1-EMUC2{slash}OC1{slash}IC1{slash}INT1{slash}RD0-Pad23)") (class "Default")
      (node (ref "IC1") (pin "23") (pinfunction "EMUC2/OC1/IC1/INT1/RD0_23") (pintype "bidirectional"))
    )
    (net (code "58") (name "unconnected-(IC1-OSC1{slash}CLKI-Pad13)") (class "Default")
      (node (ref "IC1") (pin "13") (pinfunction "OSC1/CLKI_13") (pintype "bidirectional"))
    )
    (net (code "59") (name "unconnected-(IC1-PGC{slash}EMUC{slash}U1RX{slash}SDI1{slash}SDA{slash}RF2-Pad26)") (class "Default")
      (node (ref "IC1") (pin "26") (pinfunction "PGC/EMUC/U1RX/SDI1/SDA/RF2_26") (pintype "bidirectional"))
    )
    (net (code "60") (name "unconnected-(IC1-PGD{slash}EMUD{slash}U1TX{slash}SDO1{slash}SCL{slash}RF3-Pad25)") (class "Default")
      (node (ref "IC1") (pin "25") (pinfunction "PGD/EMUD/U1TX/SDO1/SCL/RF3_25") (pintype "bidirectional"))
    )
    (net (code "61") (name "unconnected-(IC1-PWM2H{slash}RE3-Pad35)") (class "Default")
      (node (ref "IC1") (pin "35") (pinfunction "PWM2H/RE3_35") (pintype "bidirectional"))
    )
    (net (code "62") (name "unconnected-(IC1-PWM2L{slash}RE2-Pad36)") (class "Default")
      (node (ref "IC1") (pin "36") (pinfunction "PWM2L/RE2_36") (pintype "bidirectional"))
    )
    (net (code "63") (name "unconnected-(IC1-PWM3H{slash}RE5-Pad33)") (class "Default")
      (node (ref "IC1") (pin "33") (pinfunction "PWM3H/RE5_33") (pintype "bidirectional"))
    )
    (net (code "64") (name "unconnected-(IC1-PWM3L{slash}RE4-Pad34)") (class "Default")
      (node (ref "IC1") (pin "34") (pinfunction "PWM3L/RE4_34") (pintype "bidirectional"))
    )
    (net (code "65") (name "unconnected-(IC1-SCK1{slash}RF6-Pad24)") (class "Default")
      (node (ref "IC1") (pin "24") (pinfunction "SCK1/RF6_24") (pintype "bidirectional"))
    )
    (net (code "66") (name "unconnected-(IC1-U2TX{slash}CN18{slash}RF5-Pad27)") (class "Default")
      (node (ref "IC1") (pin "27") (pinfunction "U2TX/CN18/RF5_27") (pintype "bidirectional"))
    )
    (net (code "67") (name "unconnected-(IC1-VDD_2-Pad21)") (class "Default")
      (node (ref "IC1") (pin "21") (pinfunction "VDD_2_21") (pintype "bidirectional"))
    )
    (net (code "68") (name "unconnected-(IC1-VSS_2-Pad20)") (class "Default")
      (node (ref "IC1") (pin "20") (pinfunction "VSS_2_20") (pintype "bidirectional"))
    )
    (net (code "69") (name "unconnected-(IC2-IN2+-Pad5)") (class "Default")
      (node (ref "IC2") (pin "5") (pinfunction "IN2+_5") (pintype "bidirectional"))
    )
    (net (code "70") (name "unconnected-(IC2-IN2--Pad6)") (class "Default")
      (node (ref "IC2") (pin "6") (pinfunction "IN2-_6") (pintype "bidirectional"))
    )
    (net (code "71") (name "unconnected-(IC2-IN3+-Pad10)") (class "Default")
      (node (ref "IC2") (pin "10") (pinfunction "IN3+_10") (pintype "bidirectional"))
    )
    (net (code "72") (name "unconnected-(IC2-IN3--Pad9)") (class "Default")
      (node (ref "IC2") (pin "9") (pinfunction "IN3-_9") (pintype "bidirectional"))
    )
    (net (code "73") (name "unconnected-(IC2-IN4+-Pad12)") (class "Default")
      (node (ref "IC2") (pin "12") (pinfunction "IN4+_12") (pintype "bidirectional"))
    )
    (net (code "74") (name "unconnected-(IC2-IN4--Pad13)") (class "Default")
      (node (ref "IC2") (pin "13") (pinfunction "IN4-_13") (pintype "bidirectional"))
    )
    (net (code "75") (name "unconnected-(IC2-OUT2-Pad7)") (class "Default")
      (node (ref "IC2") (pin "7") (pinfunction "OUT2_7") (pintype "bidirectional"))
    )
    (net (code "76") (name "unconnected-(IC2-OUT3-Pad8)") (class "Default")
      (node (ref "IC2") (pin "8") (pinfunction "OUT3_8") (pintype "bidirectional"))
    )
    (net (code "77") (name "unconnected-(IC2-OUT4-Pad14)") (class "Default")
      (node (ref "IC2") (pin "14") (pinfunction "OUT4_14") (pintype "bidirectional"))
    )
    (net (code "78") (name "unconnected-(IC3-GND_2-Pad2)") (class "Default")
      (node (ref "IC3") (pin "2") (pinfunction "GND_2_2") (pintype "bidirectional"))
    )
    (net (code "79") (name "unconnected-(IC3-VDD_2-Pad5)") (class "Default")
      (node (ref "IC3") (pin "5") (pinfunction "VDD_2_5") (pintype "bidirectional"))
    )
    (net (code "80") (name "unconnected-(IC4-A3-Pad4)") (class "Default")
      (node (ref "IC4") (pin "4") (pinfunction "A3_4") (pintype "bidirectional"))
    )
    (net (code "81") (name "unconnected-(IC4-A4-Pad5)") (class "Default")
      (node (ref "IC4") (pin "5") (pinfunction "A4_5") (pintype "bidirectional"))
    )
    (net (code "82") (name "unconnected-(IC4-A5-Pad6)") (class "Default")
      (node (ref "IC4") (pin "6") (pinfunction "A5_6") (pintype "bidirectional"))
    )
    (net (code "83") (name "unconnected-(IC4-A6-Pad7)") (class "Default")
      (node (ref "IC4") (pin "7") (pinfunction "A6_7") (pintype "bidirectional"))
    )
    (net (code "84") (name "unconnected-(IC4-A7-Pad8)") (class "Default")
      (node (ref "IC4") (pin "8") (pinfunction "A7_8") (pintype "bidirectional"))
    )
    (net (code "85") (name "unconnected-(IC4-A8-Pad9)") (class "Default")
      (node (ref "IC4") (pin "9") (pinfunction "A8_9") (pintype "bidirectional"))
    )
    (net (code "86") (name "unconnected-(IC4-B3-Pad17)") (class "Default")
      (node (ref "IC4") (pin "17") (pinfunction "B3_17") (pintype "bidirectional"))
    )
    (net (code "87") (name "unconnected-(IC4-B4-Pad16)") (class "Default")
      (node (ref "IC4") (pin "16") (pinfunction "B4_16") (pintype "bidirectional"))
    )
    (net (code "88") (name "unconnected-(IC4-B5-Pad15)") (class "Default")
      (node (ref "IC4") (pin "15") (pinfunction "B5_15") (pintype "bidirectional"))
    )
    (net (code "89") (name "unconnected-(IC4-B6-Pad14)") (class "Default")
      (node (ref "IC4") (pin "14") (pinfunction "B6_14") (pintype "bidirectional"))
    )
    (net (code "90") (name "unconnected-(IC4-B7-Pad13)") (class "Default")
      (node (ref "IC4") (pin "13") (pinfunction "B7_13") (pintype "bidirectional"))
    )
    (net (code "91") (name "unconnected-(IC4-B8-Pad12)") (class "Default")
      (node (ref "IC4") (pin "12") (pinfunction "B8_12") (pintype "bidirectional"))
    )
    (net (code "92") (name "unconnected-(IC5-PadCTS)") (class "Default")
      (node (ref "IC5") (pin "CTS") (pinfunction "CTS_CTS") (pintype "bidirectional"))
    )
    (net (code "93") (name "unconnected-(IC5-PadGND0)") (class "Default")
      (node (ref "IC5") (pin "GND0") (pinfunction "GND0_GND0") (pintype "bidirectional"))
    )
    (net (code "94") (name "unconnected-(IC5-PadGND1)") (class "Default")
      (node (ref "IC5") (pin "GND1") (pinfunction "GND1_GND1") (pintype "bidirectional"))
    )
    (net (code "95") (name "unconnected-(IC5-PadGPIO0)") (class "Default")
      (node (ref "IC5") (pin "GPIO0") (pinfunction "GPIO0_GPIO0") (pintype "bidirectional"))
    )
    (net (code "96") (name "unconnected-(IC5-PadGPIO1)") (class "Default")
      (node (ref "IC5") (pin "GPIO1") (pinfunction "GPIO1_GPIO1") (pintype "bidirectional"))
    )
    (net (code "97") (name "unconnected-(IC5-PadGPIO2)") (class "Default")
      (node (ref "IC5") (pin "GPIO2") (pinfunction "GPIO2_GPIO2") (pintype "bidirectional"))
    )
    (net (code "98") (name "unconnected-(IC5-PadGPIO3)") (class "Default")
      (node (ref "IC5") (pin "GPIO3") (pinfunction "GPIO3_GPIO3") (pintype "bidirectional"))
    )
    (net (code "99") (name "unconnected-(IC5-PadGPIO4)") (class "Default")
      (node (ref "IC5") (pin "GPIO4") (pinfunction "GPIO4_GPIO4") (pintype "bidirectional"))
    )
    (net (code "100") (name "unconnected-(IC5-PadGPIO5)") (class "Default")
      (node (ref "IC5") (pin "GPIO5") (pinfunction "GPIO5_GPIO5") (pintype "bidirectional"))
    )
    (net (code "101") (name "unconnected-(IC5-PadGPIO6)") (class "Default")
      (node (ref "IC5") (pin "GPIO6") (pinfunction "GPIO6_GPIO6") (pintype "bidirectional"))
    )
    (net (code "102") (name "unconnected-(IC5-PadGPIO7)") (class "Default")
      (node (ref "IC5") (pin "GPIO7") (pinfunction "GPIO7_GPIO7") (pintype "bidirectional"))
    )
    (net (code "103") (name "unconnected-(IC5-PadGPIO8)") (class "Default")
      (node (ref "IC5") (pin "GPIO8") (pinfunction "GPIO8_GPIO8") (pintype "bidirectional"))
    )
    (net (code "104") (name "unconnected-(IC5-PadGPIO9)") (class "Default")
      (node (ref "IC5") (pin "GPIO9") (pinfunction "GPIO9_GPIO9") (pintype "bidirectional"))
    )
    (net (code "105") (name "unconnected-(IC5-PadGPIO10)") (class "Default")
      (node (ref "IC5") (pin "GPIO10") (pinfunction "GPIO10_GPIO10") (pintype "bidirectional"))
    )
    (net (code "106") (name "unconnected-(IC5-PadGPIO11)") (class "Default")
      (node (ref "IC5") (pin "GPIO11") (pinfunction "GPIO11_GPIO11") (pintype "bidirectional"))
    )
    (net (code "107") (name "unconnected-(IC5-PadGPIO12)") (class "Default")
      (node (ref "IC5") (pin "GPIO12") (pinfunction "GPIO12_GPIO12") (pintype "bidirectional"))
    )
    (net (code "108") (name "unconnected-(IC5-PadGPIO13)") (class "Default")
      (node (ref "IC5") (pin "GPIO13") (pinfunction "GPIO13_GPIO13") (pintype "bidirectional"))
    )
    (net (code "109") (name "unconnected-(IC5-PadMCLR)") (class "Default")
      (node (ref "IC5") (pin "MCLR") (pinfunction "MCLR_MCLR") (pintype "bidirectional"))
    )
    (net (code "110") (name "unconnected-(IC5-PadRESRV)") (class "Default")
      (node (ref "IC5") (pin "RESRV") (pinfunction "RESRV_RESRV") (pintype "bidirectional"))
    )
    (net (code "111") (name "unconnected-(IC5-PadRESRV.)") (class "Default")
      (node (ref "IC5") (pin "RESRV.") (pinfunction "RESRV._RESRV.") (pintype "bidirectional"))
    )
    (net (code "112") (name "unconnected-(IC5-PadRTS)") (class "Default")
      (node (ref "IC5") (pin "RTS") (pinfunction "RTS_RTS") (pintype "bidirectional"))
    )
    (net (code "113") (name "unconnected-(IC5-PadV3.3)") (class "Default")
      (node (ref "IC5") (pin "V3.3") (pinfunction "V3.3_V3.3") (pintype "bidirectional"))
    )
    (net (code "114") (name "unconnected-(J3-PadA2)") (class "Default")
      (node (ref "J3") (pin "A2") (pinfunction "A2_A2") (pintype "bidirectional"))
    )
    (net (code "115") (name "unconnected-(J3-PadB1)") (class "Default")
      (node (ref "J3") (pin "B1") (pinfunction "B1_B1") (pintype "bidirectional"))
    )
    (net (code "116") (name "unconnected-(J4-Pad1)") (class "Default")
      (node (ref "J4") (pin "1") (pinfunction "1_1") (pintype "bidirectional"))
    )
    (net (code "117") (name "unconnected-(J4-Pad2)") (class "Default")
      (node (ref "J4") (pin "2") (pinfunction "2_2") (pintype "bidirectional"))
    )
    (net (code "118") (name "unconnected-(R18-Pad2)") (class "Default")
      (node (ref "R18") (pin "2") (pinfunction "2_2") (pintype "bidirectional"))
    )
    (net (code "119") (name "unconnected-(S1-COM_1-PadC1)") (class "Default")
      (node (ref "S1") (pin "C1") (pinfunction "COM_1_C1") (pintype "bidirectional"))
    )
    (net (code "120") (name "unconnected-(S1-NO_1-PadA1)") (class "Default")
      (node (ref "S1") (pin "A1") (pinfunction "NO_1_A1") (pintype "bidirectional"))
    )
    (net (code "121") (name "unconnected-(S2-COM_2-PadD1)") (class "Default")
      (node (ref "S2") (pin "D1") (pinfunction "COM_2_D1") (pintype "bidirectional"))
    )
    (net (code "122") (name "unconnected-(S2-NO_2-PadB1)") (class "Default")
      (node (ref "S2") (pin "B1") (pinfunction "NO_2_B1") (pintype "bidirectional"))
    )
    (net (code "123") (name "unconnected-(S3-COM_2-PadD1)") (class "Default")
      (node (ref "S3") (pin "D1") (pinfunction "COM_2_D1") (pintype "bidirectional"))
    )
    (net (code "124") (name "unconnected-(S3-NO_2-PadB1)") (class "Default")
      (node (ref "S3") (pin "B1") (pinfunction "NO_2_B1") (pintype "bidirectional"))
    )
    (net (code "125") (name "unconnected-(S4-COM_2-PadD1)") (class "Default")
      (node (ref "S4") (pin "D1") (pinfunction "COM_2_D1") (pintype "bidirectional"))
    )
    (net (code "126") (name "unconnected-(S4-NO_2-PadB1)") (class "Default")
      (node (ref "S4") (pin "B1") (pinfunction "NO_2_B1") (pintype "bidirectional"))
    )
    (net (code "127") (name "unconnected-(T11-E-Pad3)") (class "Default")
      (node (ref "T11") (pin "3") (pinfunction "E_3") (pintype "passive"))
    )
  )
)
